# TrinketM0TopShield.net
KiCad netlist of a schematic drawn in EAGLE
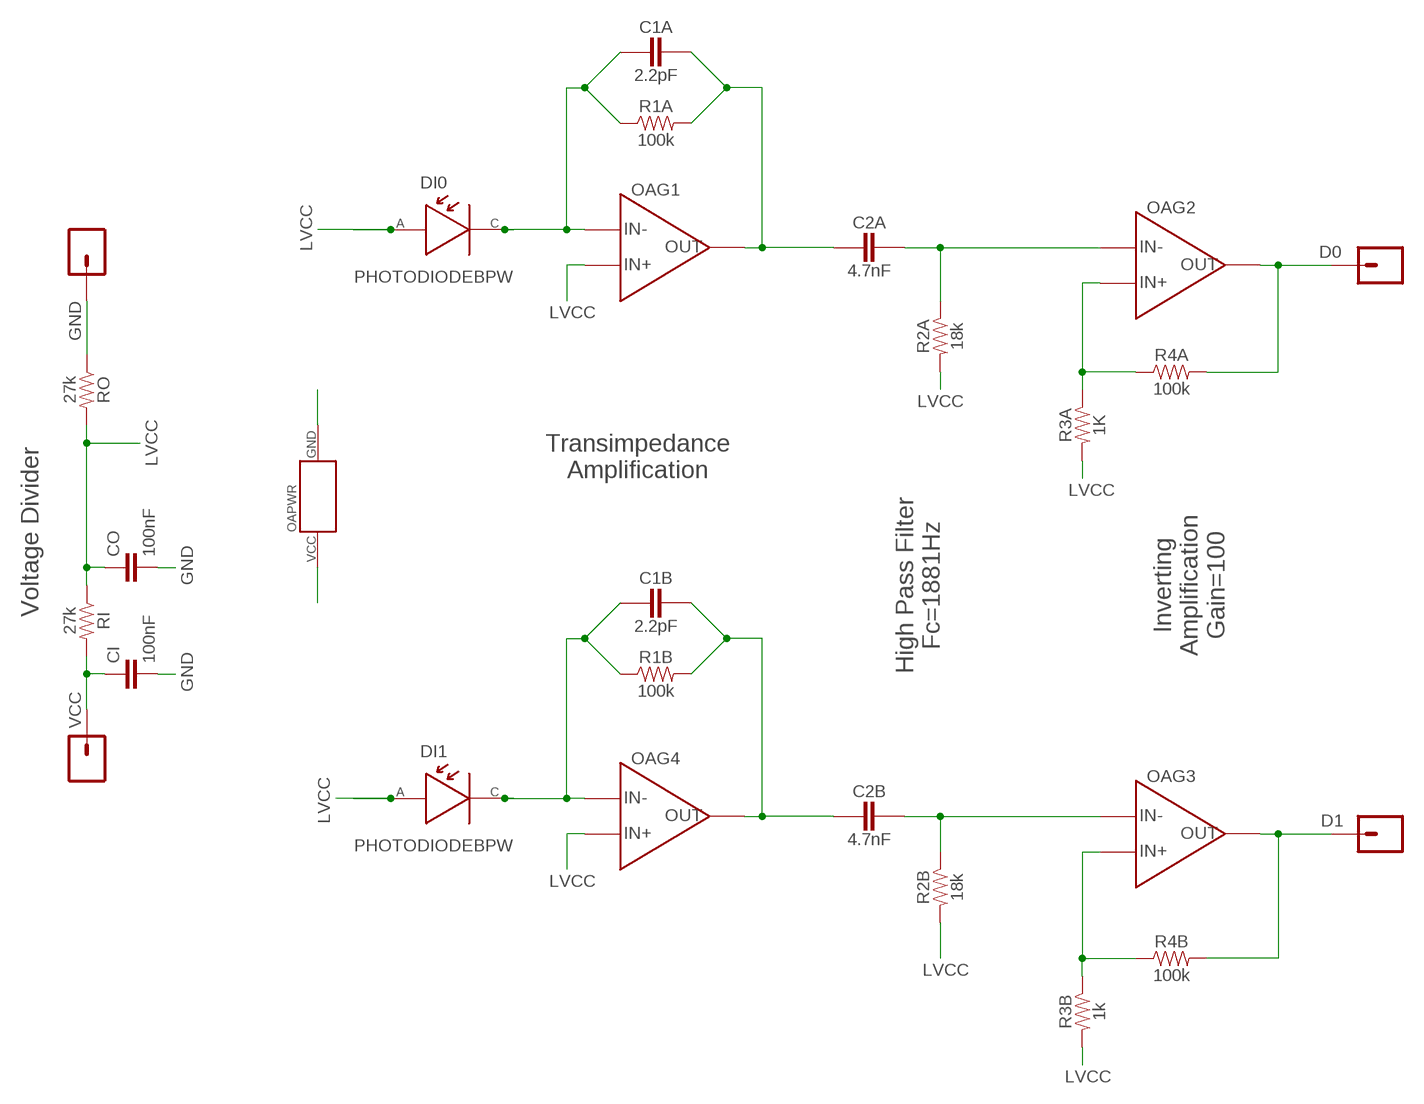
[diagram p0: schematic, sheet 1]

(export (version "E")
  (design (tool "Eeschema 10.0.6"))
  (components
    (comp (ref "C1A")
      (value "2.2pF")
      (footprint "eagle-import:PASSIVE-0603")
      (libsource (lib "eagle-import") (part "CAPACITOR"))
    )
    (comp (ref "C1B")
      (value "2.2pF")
      (footprint "eagle-import:PASSIVE-0603")
      (libsource (lib "eagle-import") (part "CAPACITOR"))
    )
    (comp (ref "C2A")
      (value "4.7nF")
      (footprint "eagle-import:PASSIVE-0603")
      (libsource (lib "eagle-import") (part "CAPACITOR"))
    )
    (comp (ref "C2B")
      (value "4.7nF")
      (footprint "eagle-import:PASSIVE-0603")
      (libsource (lib "eagle-import") (part "CAPACITOR"))
    )
    (comp (ref "CI")
      (value "100nF")
      (footprint "eagle-import:0603")
      (libsource (lib "eagle-import") (part "4.7PF-0603-50V-5%"))
    )
    (comp (ref "CO")
      (value "100nF")
      (footprint "eagle-import:0603")
      (libsource (lib "eagle-import") (part "4.7PF-0603-50V-5%"))
    )
    (comp (ref "D0")
      (value "CONN_01PTH_NO_SILK_YES_STOP")
      (footprint "eagle-import:1X01_NO_SILK")
      (libsource (lib "eagle-import") (part "CONN_01PTH_NO_SILK_YES_STOP"))
    )
    (comp (ref "D1")
      (value "CONN_01PTH_NO_SILK_YES_STOP")
      (footprint "eagle-import:1X01_NO_SILK")
      (libsource (lib "eagle-import") (part "CONN_01PTH_NO_SILK_YES_STOP"))
    )
    (comp (ref "D2")
      (value "CONN_01PTH_NO_SILK_YES_STOP")
      (footprint "eagle-import:1X01_NO_SILK")
      (libsource (lib "eagle-import") (part "CONN_01PTH_NO_SILK_YES_STOP"))
    )
    (comp (ref "DI0")
      (value "PHOTODIODEBPW")
      (footprint "eagle-import:BPW34_BP104_SMD")
      (libsource (lib "eagle-import") (part "PHOTODIODEBPW"))
    )
    (comp (ref "DI1")
      (value "PHOTODIODEBPW")
      (footprint "eagle-import:BPW34_BP104_SMD")
      (libsource (lib "eagle-import") (part "PHOTODIODEBPW"))
    )
    (comp (ref "OA")
      (value "TLV2464IPW")
      (footprint "eagle-import:PW14")
      (libsource (lib "eagle-import") (part "TLV2464IPW"))
    )
    (comp (ref "R1A")
      (value "100k")
      (footprint "eagle-import:PASSIVE-0603")
      (libsource (lib "eagle-import") (part "RESISTOR"))
    )
    (comp (ref "R1B")
      (value "100k")
      (footprint "eagle-import:PASSIVE-0603")
      (libsource (lib "eagle-import") (part "RESISTOR"))
    )
    (comp (ref "R2A")
      (value "18k")
      (footprint "eagle-import:PASSIVE-0603")
      (libsource (lib "eagle-import") (part "RESISTOR"))
    )
    (comp (ref "R2B")
      (value "18k")
      (footprint "eagle-import:PASSIVE-0603")
      (libsource (lib "eagle-import") (part "RESISTOR"))
    )
    (comp (ref "R3A")
      (value "1K")
      (footprint "eagle-import:PASSIVE-0603")
      (libsource (lib "eagle-import") (part "RESISTOR"))
    )
    (comp (ref "R3B")
      (value "1k")
      (footprint "eagle-import:PASSIVE-0603")
      (libsource (lib "eagle-import") (part "RESISTOR"))
    )
    (comp (ref "R4A")
      (value "100k")
      (footprint "eagle-import:PASSIVE-0603")
      (libsource (lib "eagle-import") (part "RESISTOR"))
    )
    (comp (ref "R4B")
      (value "100k")
      (footprint "eagle-import:PASSIVE-0603")
      (libsource (lib "eagle-import") (part "RESISTOR"))
    )
    (comp (ref "RI")
      (value "27k")
      (footprint "eagle-import:0603")
      (libsource (lib "eagle-import") (part "100KOHM-0603-1/10W-1%"))
    )
    (comp (ref "RO")
      (value "27k")
      (footprint "eagle-import:0603")
      (libsource (lib "eagle-import") (part "100KOHM-0603-1/10W-1%"))
    )
    (comp (ref "VCC")
      (value "CONN_01PTH_NO_SILK_YES_STOP")
      (footprint "eagle-import:1X01_NO_SILK")
      (libsource (lib "eagle-import") (part "CONN_01PTH_NO_SILK_YES_STOP"))
    )
  )
  (nets
    (net (code "1") (name "/D0") (class "Default")
      (node (ref "D0") (pin "1") (pinfunction "1_1") (pintype "passive"))
      (node (ref "OA") (pin "7") (pinfunction "OUT_7") (pintype "bidirectional"))
      (node (ref "R4A") (pin "2") (pinfunction "2_2") (pintype "passive"))
    )
    (net (code "2") (name "/D1") (class "Default")
      (node (ref "D1") (pin "1") (pinfunction "1_1") (pintype "passive"))
      (node (ref "OA") (pin "8") (pinfunction "OUT_8") (pintype "bidirectional"))
      (node (ref "R4B") (pin "2") (pinfunction "2_2") (pintype "passive"))
    )
    (net (code "3") (name "/GND") (class "Default")
      (node (ref "CI") (pin "2") (pinfunction "2_2") (pintype "passive"))
      (node (ref "CO") (pin "2") (pinfunction "2_2") (pintype "passive"))
      (node (ref "D2") (pin "1") (pinfunction "1_1") (pintype "passive"))
      (node (ref "OA") (pin "11") (pinfunction "GND_11") (pintype "bidirectional"))
      (node (ref "RO") (pin "1") (pinfunction "1_1") (pintype "passive"))
    )
    (net (code "4") (name "/LVCC") (class "Default")
      (node (ref "CO") (pin "1") (pinfunction "1_1") (pintype "passive"))
      (node (ref "DI0") (pin "ANODE") (pinfunction "ANODE_ANODE") (pintype "bidirectional"))
      (node (ref "DI1") (pin "ANODE") (pinfunction "ANODE_ANODE") (pintype "bidirectional"))
      (node (ref "OA") (pin "12") (pinfunction "IN+_12") (pintype "bidirectional"))
      (node (ref "OA") (pin "3") (pinfunction "IN+_3") (pintype "bidirectional"))
      (node (ref "R2A") (pin "2") (pinfunction "2_2") (pintype "passive"))
      (node (ref "R2B") (pin "2") (pinfunction "2_2") (pintype "passive"))
      (node (ref "R3A") (pin "2") (pinfunction "2_2") (pintype "passive"))
      (node (ref "R3B") (pin "2") (pinfunction "2_2") (pintype "passive"))
      (node (ref "RI") (pin "1") (pinfunction "1_1") (pintype "passive"))
      (node (ref "RO") (pin "2") (pinfunction "2_2") (pintype "passive"))
    )
    (net (code "5") (name "/VCC") (class "Default")
      (node (ref "CI") (pin "1") (pinfunction "1_1") (pintype "passive"))
      (node (ref "OA") (pin "4") (pinfunction "VCC_4") (pintype "bidirectional"))
      (node (ref "RI") (pin "2") (pinfunction "2_2") (pintype "passive"))
      (node (ref "VCC") (pin "1") (pinfunction "1_1") (pintype "passive"))
    )
    (net (code "6") (name "Net-(OAA-IN-)") (class "Default")
      (node (ref "C1A") (pin "1") (pinfunction "1_1") (pintype "passive"))
      (node (ref "DI0") (pin "CATHODE") (pinfunction "CATHODE_CATHODE") (pintype "bidirectional"))
      (node (ref "OA") (pin "2") (pinfunction "IN-_2") (pintype "bidirectional"))
      (node (ref "R1A") (pin "1") (pinfunction "1_1") (pintype "passive"))
    )
    (net (code "7") (name "Net-(OAA-OUT)") (class "Default")
      (node (ref "C1A") (pin "2") (pinfunction "2_2") (pintype "passive"))
      (node (ref "C2A") (pin "1") (pinfunction "1_1") (pintype "passive"))
      (node (ref "OA") (pin "1") (pinfunction "OUT_1") (pintype "bidirectional"))
      (node (ref "R1A") (pin "2") (pinfunction "2_2") (pintype "passive"))
    )
    (net (code "8") (name "Net-(OAB-IN+)") (class "Default")
      (node (ref "OA") (pin "5") (pinfunction "IN+_5") (pintype "bidirectional"))
      (node (ref "R3A") (pin "1") (pinfunction "1_1") (pintype "passive"))
      (node (ref "R4A") (pin "1") (pinfunction "1_1") (pintype "passive"))
    )
    (net (code "9") (name "Net-(OAB-IN-)") (class "Default")
      (node (ref "C2A") (pin "2") (pinfunction "2_2") (pintype "passive"))
      (node (ref "OA") (pin "6") (pinfunction "IN-_6") (pintype "bidirectional"))
      (node (ref "R2A") (pin "1") (pinfunction "1_1") (pintype "passive"))
    )
    (net (code "10") (name "Net-(OAC-IN+)") (class "Default")
      (node (ref "OA") (pin "10") (pinfunction "IN+_10") (pintype "bidirectional"))
      (node (ref "R3B") (pin "1") (pinfunction "1_1") (pintype "passive"))
      (node (ref "R4B") (pin "1") (pinfunction "1_1") (pintype "passive"))
    )
    (net (code "11") (name "Net-(OAC-IN-)") (class "Default")
      (node (ref "C2B") (pin "2") (pinfunction "2_2") (pintype "passive"))
      (node (ref "OA") (pin "9") (pinfunction "IN-_9") (pintype "bidirectional"))
      (node (ref "R2B") (pin "1") (pinfunction "1_1") (pintype "passive"))
    )
    (net (code "12") (name "Net-(OAD-IN-)") (class "Default")
      (node (ref "C1B") (pin "1") (pinfunction "1_1") (pintype "passive"))
      (node (ref "DI1") (pin "CATHODE") (pinfunction "CATHODE_CATHODE") (pintype "bidirectional"))
      (node (ref "OA") (pin "13") (pinfunction "IN-_13") (pintype "bidirectional"))
      (node (ref "R1B") (pin "1") (pinfunction "1_1") (pintype "passive"))
    )
    (net (code "13") (name "Net-(OAD-OUT)") (class "Default")
      (node (ref "C1B") (pin "2") (pinfunction "2_2") (pintype "passive"))
      (node (ref "C2B") (pin "1") (pinfunction "1_1") (pintype "passive"))
      (node (ref "OA") (pin "14") (pinfunction "OUT_14") (pintype "bidirectional"))
      (node (ref "R1B") (pin "2") (pinfunction "2_2") (pintype "passive"))
    )
  )
)
